# schematic-EasyEDA.net
KiCad netlist of a schematic drawn in EasyEDA
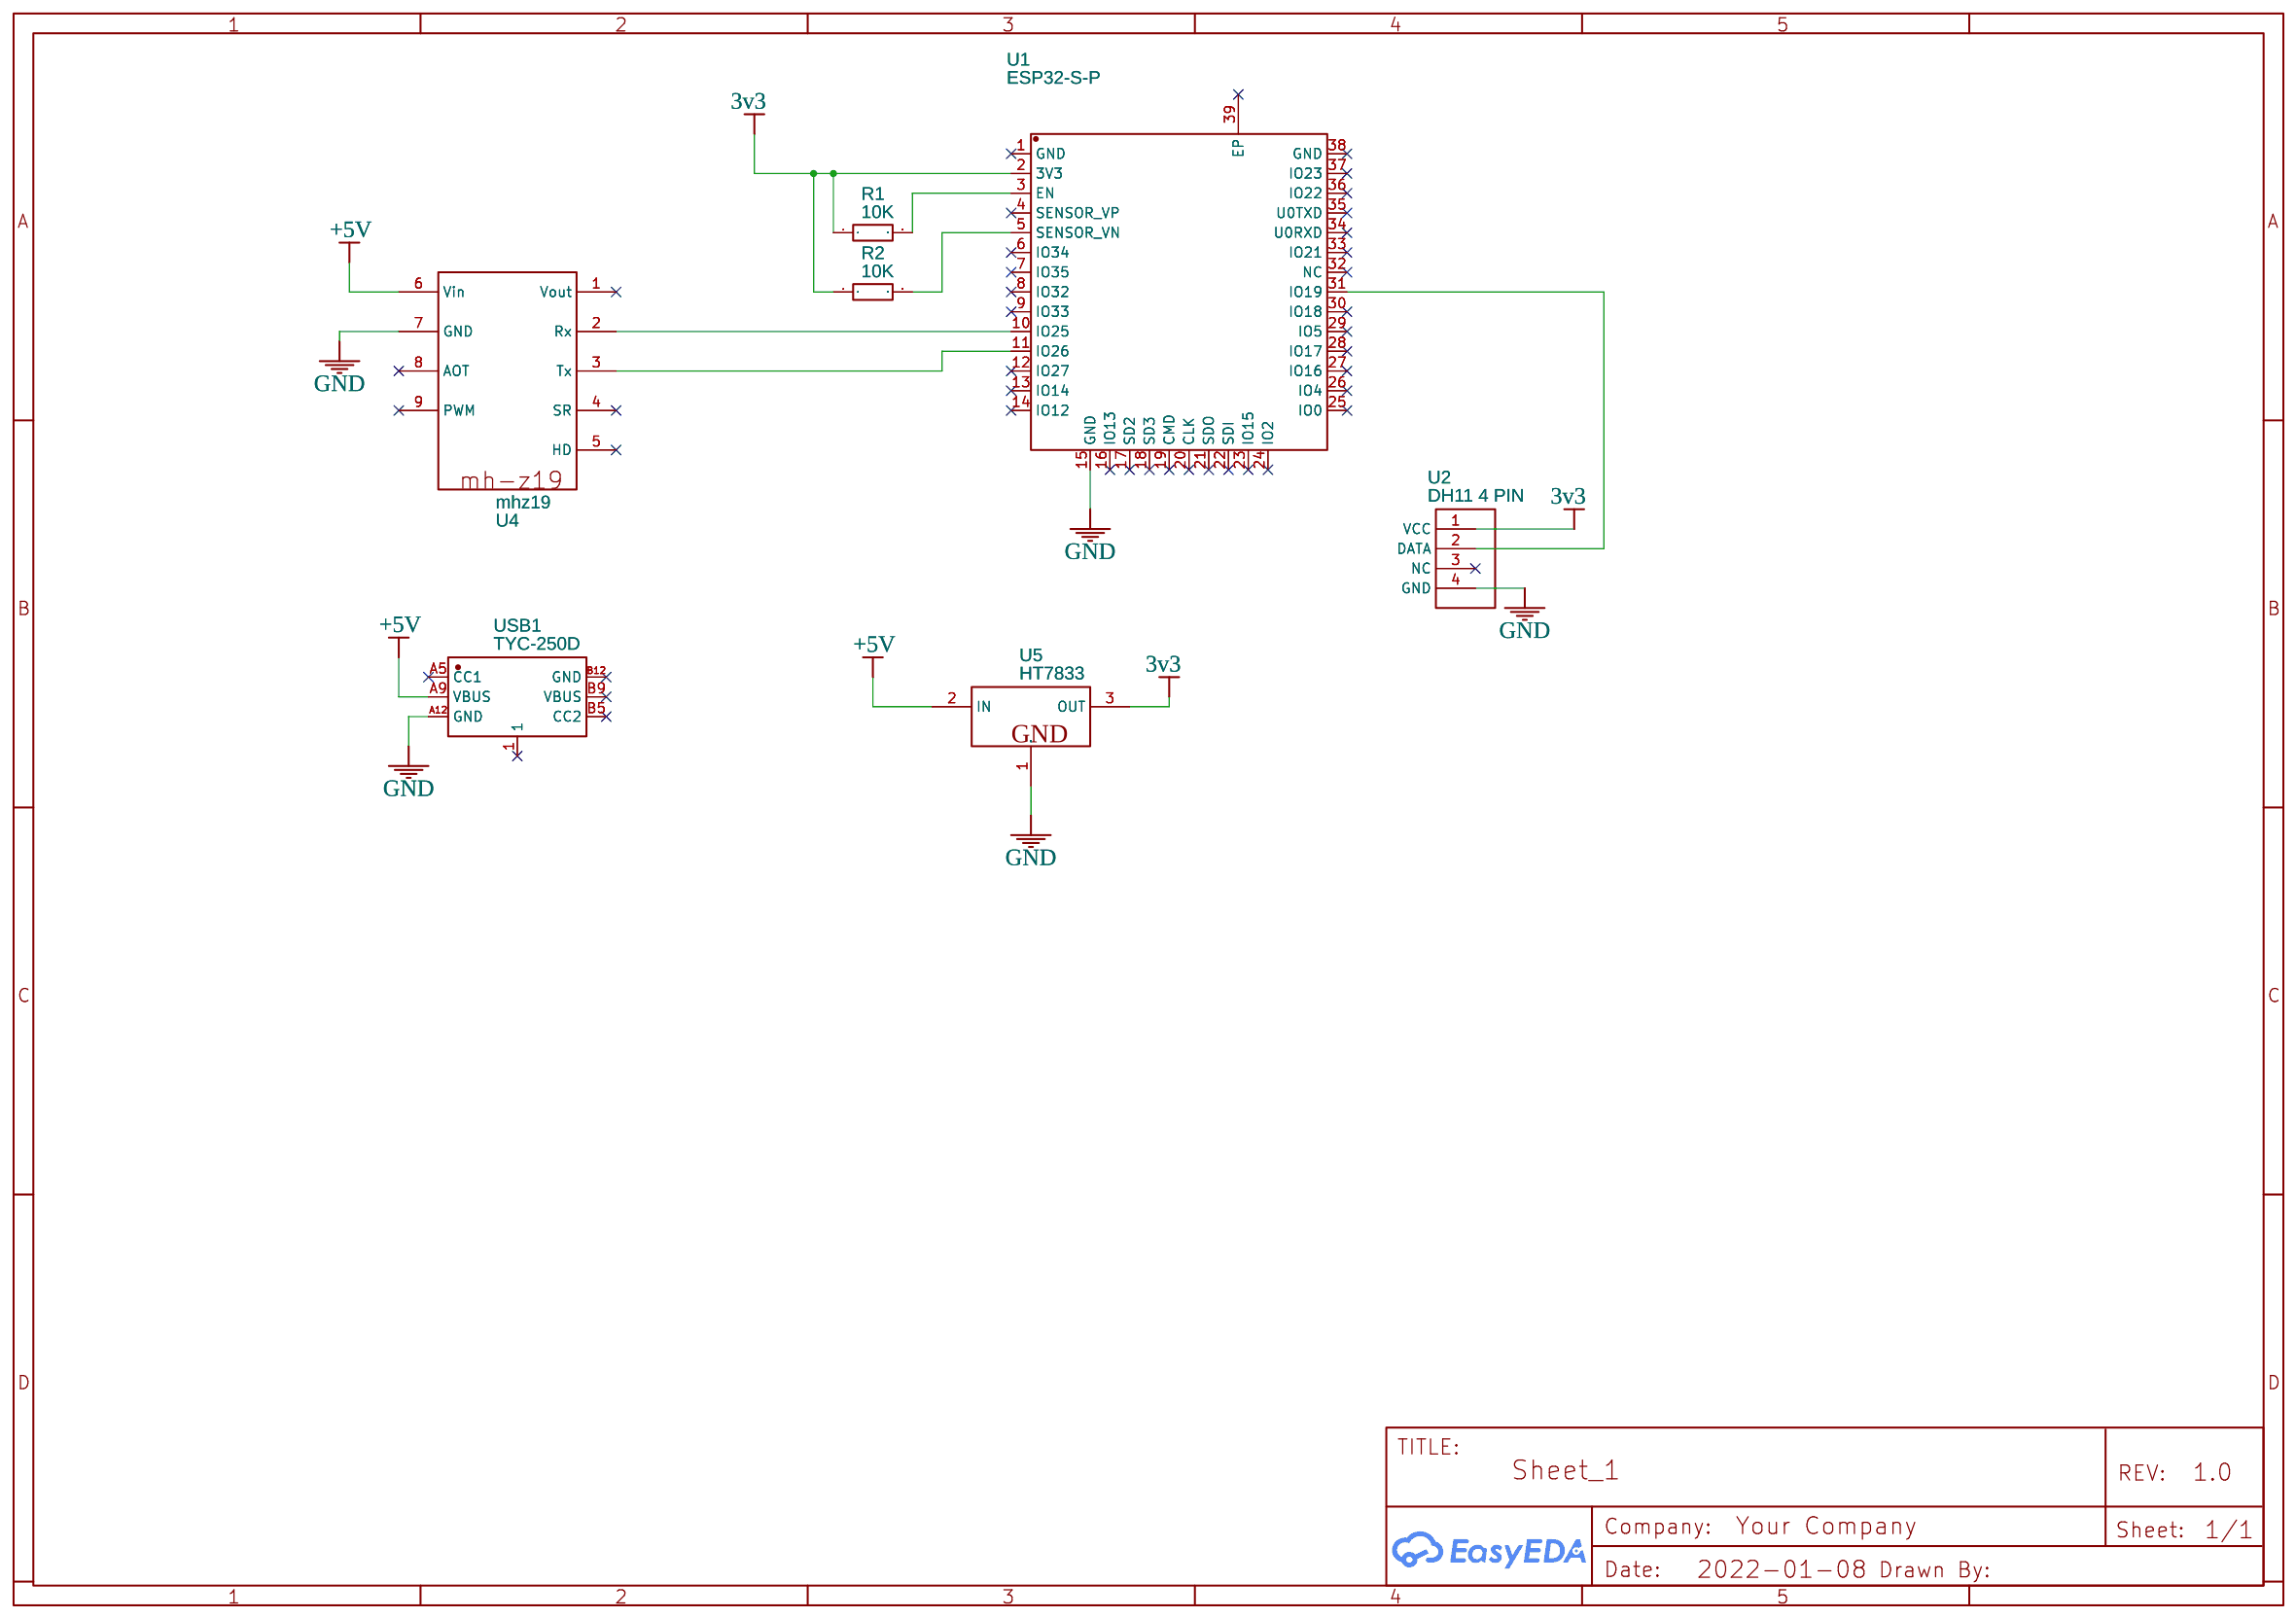
[diagram p0: schematic sheet]

(export (version "E")
  (design (tool "Eeschema 10.0.6"))
  (components
    (comp (ref "R1")
      (value "10K")
      (fields (field (name "BOM_Manufacturer Part") "1623925-3") (field (name "BOM_Supplier Part") "C306261"))
      (libsource (lib "") (part "1623925-3"))
    )
    (comp (ref "R2")
      (value "10K")
      (fields (field (name "BOM_Manufacturer Part") "1623925-3") (field (name "BOM_Supplier Part") "C306261"))
      (libsource (lib "") (part "1623925-3"))
    )
    (comp (ref "U1")
      (value "ESP32-S-P")
      (fields (field (name "BOM_Supplier Part") "C2764350"))
      (libsource (lib "") (part "ESP32-S-P"))
    )
    (comp (ref "U2") (value "DH11 4 PIN") (libsource (lib "") (part "DH11 4 PIN")))
    (comp (ref "U4") (value "mhz19") (libsource (lib "") (part "mhz19")))
    (comp (ref "U5") (value "HT7833") (libsource (lib "") (part "HT7333")))
    (comp (ref "USB1")
      (value "TYC-250D")
      (fields (field (name "BOM_Supplier Part") "C381470"))
      (libsource (lib "") (part "TYC-250D"))
    )
  )
  (nets
    (net (code "1") (name "+5V") (class "Default")
      (node (ref "U4") (pin "6") (pinfunction "Vin_6") (pintype "unspecified"))
      (node (ref "U5") (pin "2") (pinfunction "IN_2") (pintype "passive"))
      (node (ref "USB1") (pin "A9") (pinfunction "VBUS_A9") (pintype "unspecified"))
    )
    (net (code "2") (name "3v3") (class "Default")
      (node (ref "R1") (pin "1") (pinfunction "1_1") (pintype "unspecified"))
      (node (ref "R2") (pin "1") (pinfunction "1_1") (pintype "unspecified"))
      (node (ref "U1") (pin "2") (pinfunction "3V3_2") (pintype "unspecified"))
      (node (ref "U2") (pin "1") (pinfunction "VCC_1") (pintype "unspecified"))
      (node (ref "U5") (pin "3") (pinfunction "OUT_3") (pintype "passive"))
    )
    (net (code "3") (name "GND") (class "Default")
      (node (ref "U1") (pin "15") (pinfunction "GND_15") (pintype "unspecified"))
      (node (ref "U2") (pin "4") (pinfunction "GND_4") (pintype "unspecified"))
      (node (ref "U4") (pin "7") (pinfunction "GND_7") (pintype "unspecified"))
      (node (ref "U5") (pin "1") (pinfunction "GND_1") (pintype "passive"))
      (node (ref "USB1") (pin "A12") (pinfunction "GND_A12") (pintype "unspecified"))
    )
    (net (code "4") (name "Net-(U1-EN)") (class "Default")
      (node (ref "R1") (pin "2") (pinfunction "2_2") (pintype "unspecified"))
      (node (ref "U1") (pin "3") (pinfunction "EN_3") (pintype "unspecified"))
    )
    (net (code "5") (name "Net-(U1-IO19)") (class "Default")
      (node (ref "U1") (pin "31") (pinfunction "IO19_31") (pintype "unspecified"))
      (node (ref "U2") (pin "2") (pinfunction "DATA_2") (pintype "unspecified"))
    )
    (net (code "6") (name "Net-(U1-IO25)") (class "Default")
      (node (ref "U1") (pin "10") (pinfunction "IO25_10") (pintype "unspecified"))
      (node (ref "U4") (pin "2") (pinfunction "Rx_2") (pintype "unspecified"))
    )
    (net (code "7") (name "Net-(U1-IO26)") (class "Default")
      (node (ref "U1") (pin "11") (pinfunction "IO26_11") (pintype "unspecified"))
      (node (ref "U4") (pin "3") (pinfunction "Tx_3") (pintype "unspecified"))
    )
    (net (code "8") (name "Net-(U1-SENSOR_VN)") (class "Default")
      (node (ref "R2") (pin "2") (pinfunction "2_2") (pintype "unspecified"))
      (node (ref "U1") (pin "5") (pinfunction "SENSOR_VN_5") (pintype "unspecified"))
    )
    (net (code "9") (name "unconnected-(U1-CLK-Pad20)") (class "Default")
      (node (ref "U1") (pin "20") (pinfunction "CLK_20") (pintype "unspecified+no_connect"))
    )
    (net (code "10") (name "unconnected-(U1-CMD-Pad19)") (class "Default")
      (node (ref "U1") (pin "19") (pinfunction "CMD_19") (pintype "unspecified+no_connect"))
    )
    (net (code "11") (name "unconnected-(U1-EP-Pad39)") (class "Default")
      (node (ref "U1") (pin "39") (pinfunction "EP_39") (pintype "unspecified+no_connect"))
    )
    (net (code "12") (name "unconnected-(U1-GND-Pad1)") (class "Default")
      (node (ref "U1") (pin "1") (pinfunction "GND_1") (pintype "unspecified+no_connect"))
    )
    (net (code "13") (name "unconnected-(U1-GND-Pad38)") (class "Default")
      (node (ref "U1") (pin "38") (pinfunction "GND_38") (pintype "unspecified+no_connect"))
    )
    (net (code "14") (name "unconnected-(U1-IO0-Pad25)") (class "Default")
      (node (ref "U1") (pin "25") (pinfunction "IO0_25") (pintype "unspecified+no_connect"))
    )
    (net (code "15") (name "unconnected-(U1-IO2-Pad24)") (class "Default")
      (node (ref "U1") (pin "24") (pinfunction "IO2_24") (pintype "unspecified+no_connect"))
    )
    (net (code "16") (name "unconnected-(U1-IO4-Pad26)") (class "Default")
      (node (ref "U1") (pin "26") (pinfunction "IO4_26") (pintype "unspecified+no_connect"))
    )
    (net (code "17") (name "unconnected-(U1-IO5-Pad29)") (class "Default")
      (node (ref "U1") (pin "29") (pinfunction "IO5_29") (pintype "unspecified+no_connect"))
    )
    (net (code "18") (name "unconnected-(U1-IO12-Pad14)") (class "Default")
      (node (ref "U1") (pin "14") (pinfunction "IO12_14") (pintype "unspecified+no_connect"))
    )
    (net (code "19") (name "unconnected-(U1-IO13-Pad16)") (class "Default")
      (node (ref "U1") (pin "16") (pinfunction "IO13_16") (pintype "unspecified+no_connect"))
    )
    (net (code "20") (name "unconnected-(U1-IO14-Pad13)") (class "Default")
      (node (ref "U1") (pin "13") (pinfunction "IO14_13") (pintype "unspecified+no_connect"))
    )
    (net (code "21") (name "unconnected-(U1-IO15-Pad23)") (class "Default")
      (node (ref "U1") (pin "23") (pinfunction "IO15_23") (pintype "unspecified+no_connect"))
    )
    (net (code "22") (name "unconnected-(U1-IO16-Pad27)") (class "Default")
      (node (ref "U1") (pin "27") (pinfunction "IO16_27") (pintype "unspecified+no_connect"))
    )
    (net (code "23") (name "unconnected-(U1-IO17-Pad28)") (class "Default")
      (node (ref "U1") (pin "28") (pinfunction "IO17_28") (pintype "unspecified+no_connect"))
    )
    (net (code "24") (name "unconnected-(U1-IO18-Pad30)") (class "Default")
      (node (ref "U1") (pin "30") (pinfunction "IO18_30") (pintype "unspecified+no_connect"))
    )
    (net (code "25") (name "unconnected-(U1-IO21-Pad33)") (class "Default")
      (node (ref "U1") (pin "33") (pinfunction "IO21_33") (pintype "unspecified+no_connect"))
    )
    (net (code "26") (name "unconnected-(U1-IO22-Pad36)") (class "Default")
      (node (ref "U1") (pin "36") (pinfunction "IO22_36") (pintype "unspecified+no_connect"))
    )
    (net (code "27") (name "unconnected-(U1-IO23-Pad37)") (class "Default")
      (node (ref "U1") (pin "37") (pinfunction "IO23_37") (pintype "unspecified+no_connect"))
    )
    (net (code "28") (name "unconnected-(U1-IO27-Pad12)") (class "Default")
      (node (ref "U1") (pin "12") (pinfunction "IO27_12") (pintype "unspecified+no_connect"))
    )
    (net (code "29") (name "unconnected-(U1-IO32-Pad8)") (class "Default")
      (node (ref "U1") (pin "8") (pinfunction "IO32_8") (pintype "unspecified+no_connect"))
    )
    (net (code "30") (name "unconnected-(U1-IO33-Pad9)") (class "Default")
      (node (ref "U1") (pin "9") (pinfunction "IO33_9") (pintype "unspecified+no_connect"))
    )
    (net (code "31") (name "unconnected-(U1-IO34-Pad6)") (class "Default")
      (node (ref "U1") (pin "6") (pinfunction "IO34_6") (pintype "unspecified+no_connect"))
    )
    (net (code "32") (name "unconnected-(U1-IO35-Pad7)") (class "Default")
      (node (ref "U1") (pin "7") (pinfunction "IO35_7") (pintype "unspecified+no_connect"))
    )
    (net (code "33") (name "unconnected-(U1-NC-Pad32)") (class "Default")
      (node (ref "U1") (pin "32") (pinfunction "NC_32") (pintype "unspecified+no_connect"))
    )
    (net (code "34") (name "unconnected-(U1-SD2-Pad17)") (class "Default")
      (node (ref "U1") (pin "17") (pinfunction "SD2_17") (pintype "unspecified+no_connect"))
    )
    (net (code "35") (name "unconnected-(U1-SD3-Pad18)") (class "Default")
      (node (ref "U1") (pin "18") (pinfunction "SD3_18") (pintype "unspecified+no_connect"))
    )
    (net (code "36") (name "unconnected-(U1-SDI-Pad22)") (class "Default")
      (node (ref "U1") (pin "22") (pinfunction "SDI_22") (pintype "unspecified+no_connect"))
    )
    (net (code "37") (name "unconnected-(U1-SDO-Pad21)") (class "Default")
      (node (ref "U1") (pin "21") (pinfunction "SDO_21") (pintype "unspecified+no_connect"))
    )
    (net (code "38") (name "unconnected-(U1-SENSOR_VP-Pad4)") (class "Default")
      (node (ref "U1") (pin "4") (pinfunction "SENSOR_VP_4") (pintype "unspecified+no_connect"))
    )
    (net (code "39") (name "unconnected-(U1-U0RXD-Pad34)") (class "Default")
      (node (ref "U1") (pin "34") (pinfunction "U0RXD_34") (pintype "unspecified+no_connect"))
    )
    (net (code "40") (name "unconnected-(U1-U0TXD-Pad35)") (class "Default")
      (node (ref "U1") (pin "35") (pinfunction "U0TXD_35") (pintype "unspecified+no_connect"))
    )
    (net (code "41") (name "unconnected-(U2-NC-Pad3)") (class "Default")
      (node (ref "U2") (pin "3") (pinfunction "NC_3") (pintype "unspecified+no_connect"))
    )
    (net (code "42") (name "unconnected-(U4-AOT-Pad8)") (class "Default")
      (node (ref "U4") (pin "8") (pinfunction "AOT_8") (pintype "unspecified+no_connect"))
    )
    (net (code "43") (name "unconnected-(U4-HD-Pad5)") (class "Default")
      (node (ref "U4") (pin "5") (pinfunction "HD_5") (pintype "unspecified+no_connect"))
    )
    (net (code "44") (name "unconnected-(U4-PWM-Pad9)") (class "Default")
      (node (ref "U4") (pin "9") (pinfunction "PWM_9") (pintype "unspecified+no_connect"))
    )
    (net (code "45") (name "unconnected-(U4-SR-Pad4)") (class "Default")
      (node (ref "U4") (pin "4") (pinfunction "SR_4") (pintype "unspecified+no_connect"))
    )
    (net (code "46") (name "unconnected-(U4-Vout-Pad1)") (class "Default")
      (node (ref "U4") (pin "1") (pinfunction "Vout_1") (pintype "unspecified+no_connect"))
    )
    (net (code "47") (name "unconnected-(USB1-CC1-PadA5)") (class "Default")
      (node (ref "USB1") (pin "A5") (pinfunction "CC1_A5") (pintype "unspecified+no_connect"))
    )
    (net (code "48") (name "unconnected-(USB1-CC2-PadB5)") (class "Default")
      (node (ref "USB1") (pin "B5") (pinfunction "CC2_B5") (pintype "unspecified+no_connect"))
    )
    (net (code "49") (name "unconnected-(USB1-GND-PadB12)") (class "Default")
      (node (ref "USB1") (pin "B12") (pinfunction "GND_B12") (pintype "unspecified+no_connect"))
    )
    (net (code "50") (name "unconnected-(USB1-Pad1)") (class "Default")
      (node (ref "USB1") (pin "1") (pinfunction "1_1") (pintype "unspecified+no_connect"))
    )
    (net (code "51") (name "unconnected-(USB1-VBUS-PadB9)") (class "Default")
      (node (ref "USB1") (pin "B9") (pinfunction "VBUS_B9") (pintype "unspecified+no_connect"))
    )
  )
)
